# Enclosure_Front_9LED.net
KiCad netlist of a schematic drawn in EAGLE
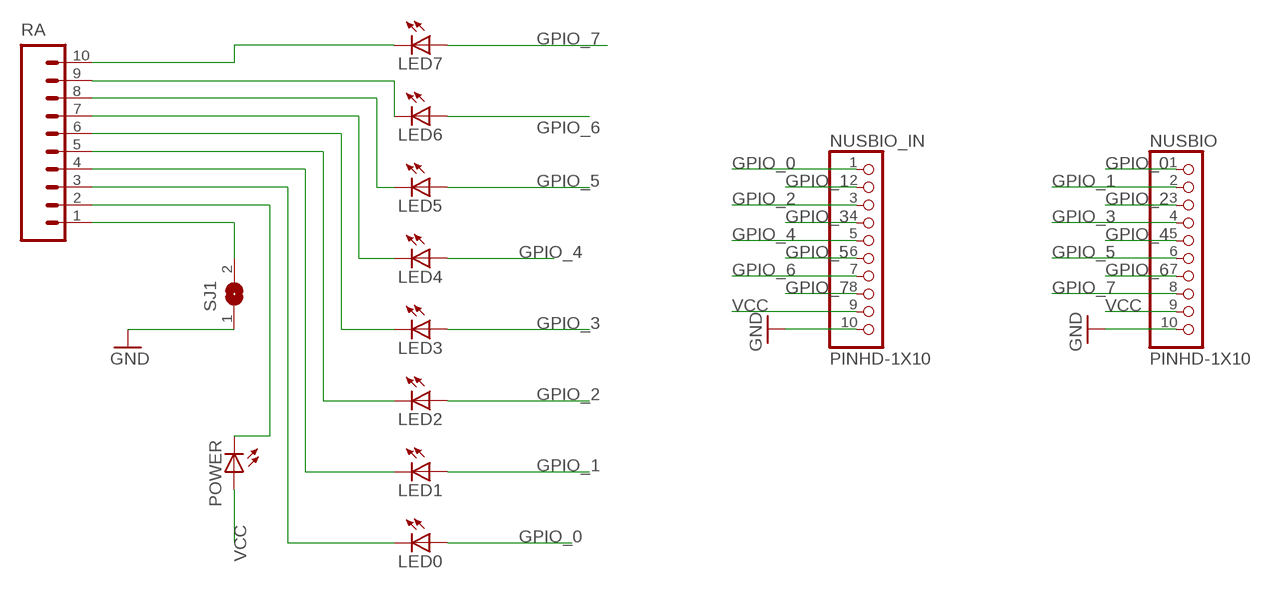
[diagram p0: schematic, sheet 1]

(export (version "E")
  (design (tool "Eeschema 10.0.6"))
  (components
    (comp (ref "LED0")
      (value "LEDSMT1206")
      (footprint "eagle-import:1206")
      (libsource (lib "eagle-import") (part "LEDSMT1206"))
    )
    (comp (ref "LED1")
      (value "LEDSMT1206")
      (footprint "eagle-import:1206")
      (libsource (lib "eagle-import") (part "LEDSMT1206"))
    )
    (comp (ref "LED2")
      (value "LEDSMT1206")
      (footprint "eagle-import:1206")
      (libsource (lib "eagle-import") (part "LEDSMT1206"))
    )
    (comp (ref "LED3")
      (value "LEDSMT1206")
      (footprint "eagle-import:1206")
      (libsource (lib "eagle-import") (part "LEDSMT1206"))
    )
    (comp (ref "LED4")
      (value "LEDSMT1206")
      (footprint "eagle-import:1206")
      (libsource (lib "eagle-import") (part "LEDSMT1206"))
    )
    (comp (ref "LED5")
      (value "LEDSMT1206")
      (footprint "eagle-import:1206")
      (libsource (lib "eagle-import") (part "LEDSMT1206"))
    )
    (comp (ref "LED6")
      (value "LEDSMT1206")
      (footprint "eagle-import:1206")
      (libsource (lib "eagle-import") (part "LEDSMT1206"))
    )
    (comp (ref "LED7")
      (value "LEDSMT1206")
      (footprint "eagle-import:1206")
      (libsource (lib "eagle-import") (part "LEDSMT1206"))
    )
    (comp (ref "NUSBIO")
      (value "PINHD-1X10")
      (footprint "eagle-import:1X10-BIG")
      (libsource (lib "eagle-import") (part "PINHD-1X10"))
    )
    (comp (ref "NUSBIO_IN")
      (value "PINHD-1X10")
      (footprint "eagle-import:1X10-BIG")
      (libsource (lib "eagle-import") (part "PINHD-1X10"))
    )
    (comp (ref "POWER")
      (value "LEDSMT1206")
      (footprint "eagle-import:1206")
      (libsource (lib "eagle-import") (part "LEDSMT1206"))
    )
    (comp (ref "RA")
      (value "M10SMD_MALE")
      (footprint "eagle-import:1X10_SMD_MALE")
      (libsource (lib "eagle-import") (part "M10SMD_MALE"))
    )
    (comp (ref "SJ1")
      (value "SOLDERJUMPERREFLOW_NOPASTE")
      (footprint "eagle-import:SOLDERJUMPER_REFLOW_NOPASTE")
      (libsource (lib "eagle-import") (part "SOLDERJUMPERREFLOW_NOPASTE"))
    )
  )
  (nets
    (net (code "1") (name "/GPIO_0") (class "Default")
      (node (ref "LED0") (pin "A") (pinfunction "A_A") (pintype "passive"))
      (node (ref "NUSBIO") (pin "1") (pinfunction "1_1") (pintype "passive"))
      (node (ref "NUSBIO_IN") (pin "1") (pinfunction "1_1") (pintype "passive"))
    )
    (net (code "2") (name "/GPIO_1") (class "Default")
      (node (ref "LED1") (pin "A") (pinfunction "A_A") (pintype "passive"))
      (node (ref "NUSBIO") (pin "2") (pinfunction "2_2") (pintype "passive"))
      (node (ref "NUSBIO_IN") (pin "2") (pinfunction "2_2") (pintype "passive"))
    )
    (net (code "3") (name "/GPIO_2") (class "Default")
      (node (ref "LED2") (pin "A") (pinfunction "A_A") (pintype "passive"))
      (node (ref "NUSBIO") (pin "3") (pinfunction "3_3") (pintype "passive"))
      (node (ref "NUSBIO_IN") (pin "3") (pinfunction "3_3") (pintype "passive"))
    )
    (net (code "4") (name "/GPIO_3") (class "Default")
      (node (ref "LED3") (pin "A") (pinfunction "A_A") (pintype "passive"))
      (node (ref "NUSBIO") (pin "4") (pinfunction "4_4") (pintype "passive"))
      (node (ref "NUSBIO_IN") (pin "4") (pinfunction "4_4") (pintype "passive"))
    )
    (net (code "5") (name "/GPIO_4") (class "Default")
      (node (ref "LED4") (pin "A") (pinfunction "A_A") (pintype "passive"))
      (node (ref "NUSBIO") (pin "5") (pinfunction "5_5") (pintype "passive"))
      (node (ref "NUSBIO_IN") (pin "5") (pinfunction "5_5") (pintype "passive"))
    )
    (net (code "6") (name "/GPIO_5") (class "Default")
      (node (ref "LED5") (pin "A") (pinfunction "A_A") (pintype "passive"))
      (node (ref "NUSBIO") (pin "6") (pinfunction "6_6") (pintype "passive"))
      (node (ref "NUSBIO_IN") (pin "6") (pinfunction "6_6") (pintype "passive"))
    )
    (net (code "7") (name "/GPIO_6") (class "Default")
      (node (ref "LED6") (pin "A") (pinfunction "A_A") (pintype "passive"))
      (node (ref "NUSBIO") (pin "7") (pinfunction "7_7") (pintype "passive"))
      (node (ref "NUSBIO_IN") (pin "7") (pinfunction "7_7") (pintype "passive"))
    )
    (net (code "8") (name "/GPIO_7") (class "Default")
      (node (ref "LED7") (pin "A") (pinfunction "A_A") (pintype "passive"))
      (node (ref "NUSBIO") (pin "8") (pinfunction "8_8") (pintype "passive"))
      (node (ref "NUSBIO_IN") (pin "8") (pinfunction "8_8") (pintype "passive"))
    )
    (net (code "9") (name "/VCC") (class "Default")
      (node (ref "NUSBIO") (pin "9") (pinfunction "9_9") (pintype "passive"))
      (node (ref "NUSBIO_IN") (pin "9") (pinfunction "9_9") (pintype "passive"))
      (node (ref "POWER") (pin "A") (pinfunction "A_A") (pintype "passive"))
    )
    (net (code "10") (name "GND") (class "Default")
      (node (ref "NUSBIO") (pin "10") (pinfunction "10_10") (pintype "passive"))
      (node (ref "NUSBIO_IN") (pin "10") (pinfunction "10_10") (pintype "passive"))
      (node (ref "SJ1") (pin "1") (pinfunction "1_1") (pintype "passive"))
    )
    (net (code "11") (name "Net-(LED0-PadC)") (class "Default")
      (node (ref "LED0") (pin "C") (pinfunction "C_C") (pintype "passive"))
      (node (ref "RA") (pin "3") (pinfunction "3_3") (pintype "passive"))
    )
    (net (code "12") (name "Net-(LED1-PadC)") (class "Default")
      (node (ref "LED1") (pin "C") (pinfunction "C_C") (pintype "passive"))
      (node (ref "RA") (pin "4") (pinfunction "4_4") (pintype "passive"))
    )
    (net (code "13") (name "Net-(LED2-PadC)") (class "Default")
      (node (ref "LED2") (pin "C") (pinfunction "C_C") (pintype "passive"))
      (node (ref "RA") (pin "5") (pinfunction "5_5") (pintype "passive"))
    )
    (net (code "14") (name "Net-(LED3-PadC)") (class "Default")
      (node (ref "LED3") (pin "C") (pinfunction "C_C") (pintype "passive"))
      (node (ref "RA") (pin "6") (pinfunction "6_6") (pintype "passive"))
    )
    (net (code "15") (name "Net-(LED4-PadC)") (class "Default")
      (node (ref "LED4") (pin "C") (pinfunction "C_C") (pintype "passive"))
      (node (ref "RA") (pin "7") (pinfunction "7_7") (pintype "passive"))
    )
    (net (code "16") (name "Net-(LED5-PadC)") (class "Default")
      (node (ref "LED5") (pin "C") (pinfunction "C_C") (pintype "passive"))
      (node (ref "RA") (pin "8") (pinfunction "8_8") (pintype "passive"))
    )
    (net (code "17") (name "Net-(LED6-PadC)") (class "Default")
      (node (ref "LED6") (pin "C") (pinfunction "C_C") (pintype "passive"))
      (node (ref "RA") (pin "9") (pinfunction "9_9") (pintype "passive"))
    )
    (net (code "18") (name "Net-(LED7-PadC)") (class "Default")
      (node (ref "LED7") (pin "C") (pinfunction "C_C") (pintype "passive"))
      (node (ref "RA") (pin "10") (pinfunction "10_10") (pintype "passive"))
    )
    (net (code "19") (name "Net-(POWER-PadC)") (class "Default")
      (node (ref "POWER") (pin "C") (pinfunction "C_C") (pintype "passive"))
      (node (ref "RA") (pin "2") (pinfunction "2_2") (pintype "passive"))
    )
    (net (code "20") (name "Net-(RA-Pad1)") (class "Default")
      (node (ref "RA") (pin "1") (pinfunction "1_1") (pintype "passive"))
      (node (ref "SJ1") (pin "2") (pinfunction "2_2") (pintype "passive"))
    )
  )
)
